# Shiftregister.net
KiCad netlist of a schematic drawn in Altium Designer
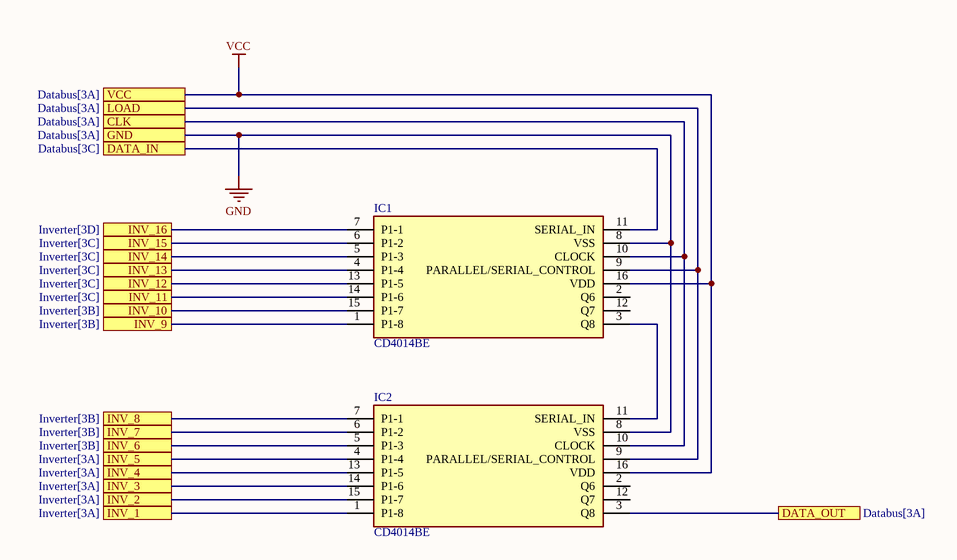
[diagram p0: Shiftregister.SchDoc]

(export (version "E")
  (design (tool "Eeschema 10.0.6"))
  (components
    (comp (ref "IC1")
      (value "CD4014BE")
      (footprint "CD4014")
      (description "Integrated Circuit")
      (fields (field (name "MOUSER PART NUMBER") "595-CD4014BE"))
      (libsource (lib "Schematic_Library_S88N") (part "CD4014BE"))
    )
    (comp (ref "IC2")
      (value "CD4014BE")
      (footprint "CD4014")
      (description "Integrated Circuit")
      (fields (field (name "MOUSER PART NUMBER") "595-CD4014BE"))
      (libsource (lib "Schematic_Library_S88N") (part "CD4014BE"))
    )
  )
  (nets
    (net (code "1") (name "/CLK") (class "Default")
      (node (ref "IC1") (pin "10") (pinfunction "CLOCK_10") (pintype "passive"))
      (node (ref "IC2") (pin "10") (pinfunction "CLOCK_10") (pintype "passive"))
    )
    (net (code "2") (name "/DATA_IN") (class "Default")
      (node (ref "IC1") (pin "11") (pinfunction "SERIAL_IN_11") (pintype "passive"))
    )
    (net (code "3") (name "/DATA_OUT") (class "Default")
      (node (ref "IC2") (pin "3") (pinfunction "Q8_3") (pintype "passive"))
    )
    (net (code "4") (name "/INV_1") (class "Default")
      (node (ref "IC2") (pin "1") (pinfunction "P1-8_1") (pintype "passive"))
    )
    (net (code "5") (name "/INV_2") (class "Default")
      (node (ref "IC2") (pin "15") (pinfunction "P1-7_15") (pintype "passive"))
    )
    (net (code "6") (name "/INV_3") (class "Default")
      (node (ref "IC2") (pin "14") (pinfunction "P1-6_14") (pintype "passive"))
    )
    (net (code "7") (name "/INV_4") (class "Default")
      (node (ref "IC2") (pin "13") (pinfunction "P1-5_13") (pintype "passive"))
    )
    (net (code "8") (name "/INV_5") (class "Default")
      (node (ref "IC2") (pin "4") (pinfunction "P1-4_4") (pintype "passive"))
    )
    (net (code "9") (name "/INV_6") (class "Default")
      (node (ref "IC2") (pin "5") (pinfunction "P1-3_5") (pintype "passive"))
    )
    (net (code "10") (name "/INV_7") (class "Default")
      (node (ref "IC2") (pin "6") (pinfunction "P1-2_6") (pintype "passive"))
    )
    (net (code "11") (name "/INV_8") (class "Default")
      (node (ref "IC2") (pin "7") (pinfunction "P1-1_7") (pintype "passive"))
    )
    (net (code "12") (name "/INV_9") (class "Default")
      (node (ref "IC1") (pin "1") (pinfunction "P1-8_1") (pintype "passive"))
    )
    (net (code "13") (name "/INV_10") (class "Default")
      (node (ref "IC1") (pin "15") (pinfunction "P1-7_15") (pintype "passive"))
    )
    (net (code "14") (name "/INV_11") (class "Default")
      (node (ref "IC1") (pin "14") (pinfunction "P1-6_14") (pintype "passive"))
    )
    (net (code "15") (name "/INV_12") (class "Default")
      (node (ref "IC1") (pin "13") (pinfunction "P1-5_13") (pintype "passive"))
    )
    (net (code "16") (name "/INV_13") (class "Default")
      (node (ref "IC1") (pin "4") (pinfunction "P1-4_4") (pintype "passive"))
    )
    (net (code "17") (name "/INV_14") (class "Default")
      (node (ref "IC1") (pin "5") (pinfunction "P1-3_5") (pintype "passive"))
    )
    (net (code "18") (name "/INV_15") (class "Default")
      (node (ref "IC1") (pin "6") (pinfunction "P1-2_6") (pintype "passive"))
    )
    (net (code "19") (name "/INV_16") (class "Default")
      (node (ref "IC1") (pin "7") (pinfunction "P1-1_7") (pintype "passive"))
    )
    (net (code "20") (name "/LOAD") (class "Default")
      (node (ref "IC1") (pin "9") (pinfunction "PARALLEL/SERIAL_CONTROL_9") (pintype "passive"))
      (node (ref "IC2") (pin "9") (pinfunction "PARALLEL/SERIAL_CONTROL_9") (pintype "passive"))
    )
    (net (code "21") (name "GND") (class "Default")
      (node (ref "IC1") (pin "8") (pinfunction "VSS_8") (pintype "passive"))
      (node (ref "IC2") (pin "8") (pinfunction "VSS_8") (pintype "passive"))
    )
    (net (code "22") (name "Net-(IC1-Q8)") (class "Default")
      (node (ref "IC1") (pin "3") (pinfunction "Q8_3") (pintype "passive"))
      (node (ref "IC2") (pin "11") (pinfunction "SERIAL_IN_11") (pintype "passive"))
    )
    (net (code "23") (name "VCC") (class "Default")
      (node (ref "IC1") (pin "16") (pinfunction "VDD_16") (pintype "passive"))
      (node (ref "IC2") (pin "16") (pinfunction "VDD_16") (pintype "passive"))
    )
    (net (code "24") (name "unconnected-(IC1-Q6-Pad2)") (class "Default")
      (node (ref "IC1") (pin "2") (pinfunction "Q6_2") (pintype "passive"))
    )
    (net (code "25") (name "unconnected-(IC1-Q7-Pad12)") (class "Default")
      (node (ref "IC1") (pin "12") (pinfunction "Q7_12") (pintype "passive"))
    )
    (net (code "26") (name "unconnected-(IC2-Q6-Pad2)") (class "Default")
      (node (ref "IC2") (pin "2") (pinfunction "Q6_2") (pintype "passive"))
    )
    (net (code "27") (name "unconnected-(IC2-Q7-Pad12)") (class "Default")
      (node (ref "IC2") (pin "12") (pinfunction "Q7_12") (pintype "passive"))
    )
  )
)
